# M1.net
KiCad netlist of a schematic drawn in Altium Designer
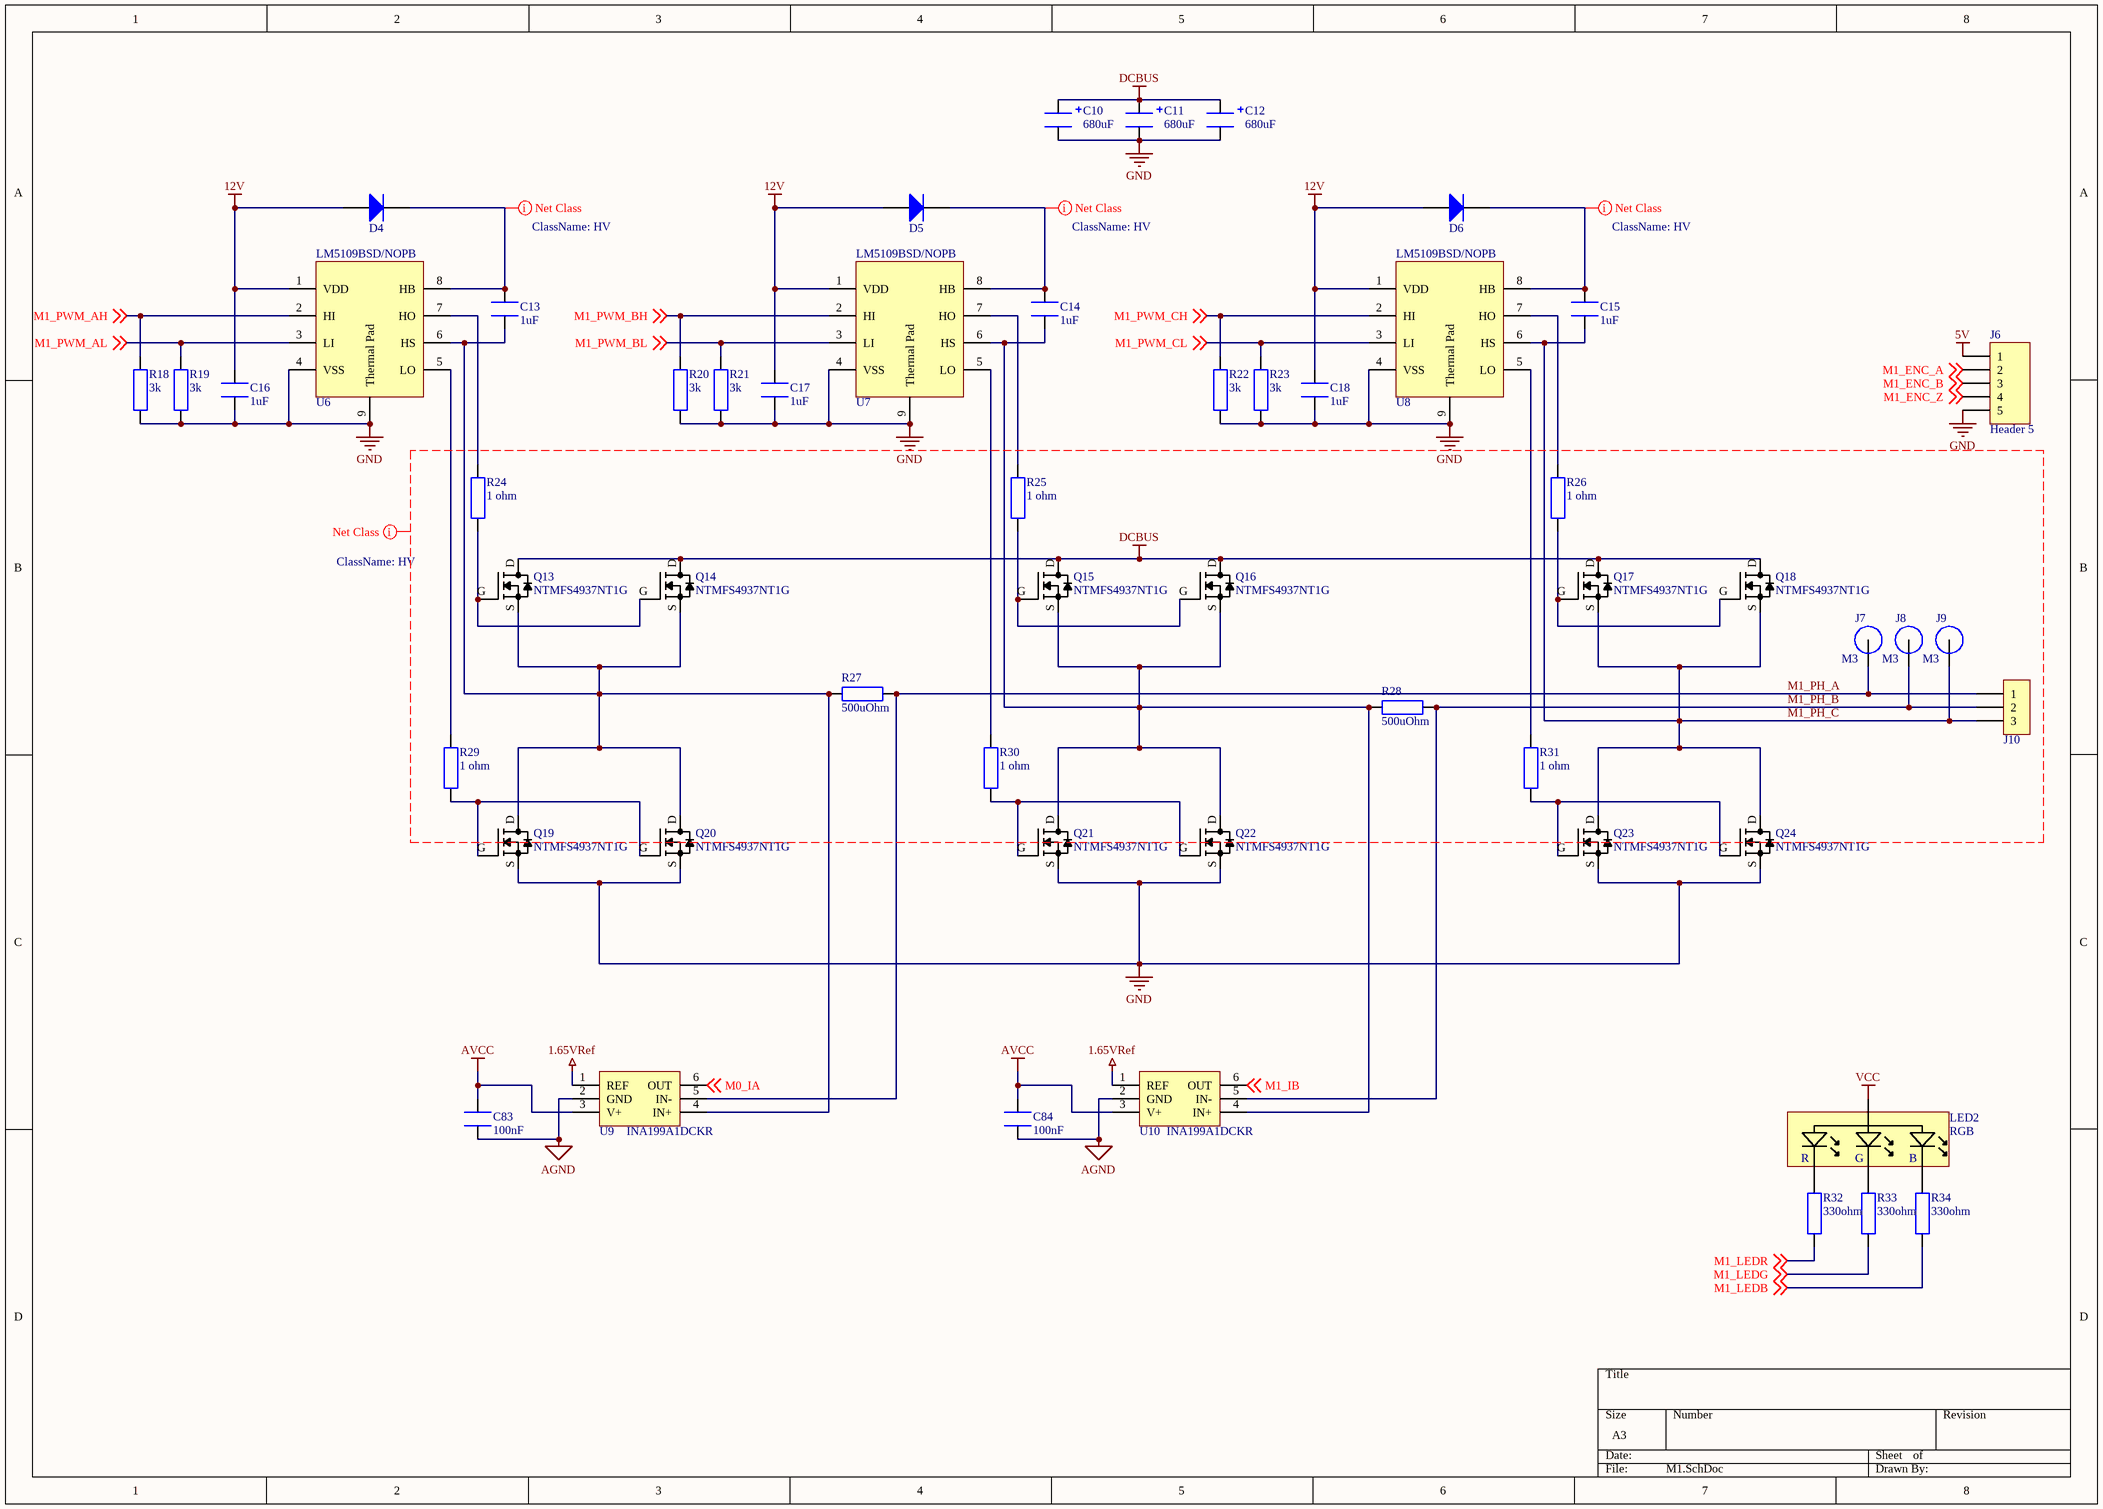
[diagram p0: M1.SchDoc]

(export (version "E")
  (design (tool "Eeschema 10.0.6"))
  (components
    (comp (ref "C10")
      (value "680uF")
      (footprint "CAPE10.0MM_Rad_10x14mm")
      (description "CAP, ALU ELEC, 680UF, 35V, RAD")
      (fields (field (name "Comment") "35ZLH680MEFC10X23"))
      (libsource (lib "CustomComponents") (part "35ZLH680MEFC10X23"))
    )
    (comp (ref "C11")
      (value "680uF")
      (footprint "CAPE10.0MM_Rad_10x14mm")
      (description "CAP, ALU ELEC, 680UF, 35V, RAD")
      (fields (field (name "Comment") "35ZLH680MEFC10X23"))
      (libsource (lib "CustomComponents") (part "35ZLH680MEFC10X23"))
    )
    (comp (ref "C12")
      (value "680uF")
      (footprint "CAPE10.0MM_Rad_10x14mm")
      (description "CAP, ALU ELEC, 680UF, 35V, RAD")
      (fields (field (name "Comment") "35ZLH680MEFC10X23"))
      (libsource (lib "CustomComponents") (part "35ZLH680MEFC10X23"))
    )
    (comp (ref "C13")
      (value "1uF")
      (footprint "1608[0603]")
      (description "CAP, MLCC, X5R, 1UF, 16V, 0603")
      (fields (field (name "Comment") "MC0603X105K160"))
      (libsource (lib "CustomComponents") (part "MC0603X105K160"))
    )
    (comp (ref "C14")
      (value "1uF")
      (footprint "1608[0603]")
      (description "CAP, MLCC, X5R, 1UF, 16V, 0603")
      (fields (field (name "Comment") "MC0603X105K160"))
      (libsource (lib "CustomComponents") (part "MC0603X105K160"))
    )
    (comp (ref "C15")
      (value "1uF")
      (footprint "1608[0603]")
      (description "CAP, MLCC, X5R, 1UF, 16V, 0603")
      (fields (field (name "Comment") "MC0603X105K160"))
      (libsource (lib "CustomComponents") (part "MC0603X105K160"))
    )
    (comp (ref "C16")
      (value "1uF")
      (footprint "1608[0603]")
      (description "CAP, MLCC, X5R, 1UF, 16V, 0603")
      (fields (field (name "Comment") "MC0603X105K160"))
      (libsource (lib "CustomComponents") (part "MC0603X105K160"))
    )
    (comp (ref "C17")
      (value "1uF")
      (footprint "1608[0603]")
      (description "CAP, MLCC, X5R, 1UF, 16V, 0603")
      (fields (field (name "Comment") "MC0603X105K160"))
      (libsource (lib "CustomComponents") (part "MC0603X105K160"))
    )
    (comp (ref "C18")
      (value "1uF")
      (footprint "1608[0603]")
      (description "CAP, MLCC, X5R, 1UF, 16V, 0603")
      (fields (field (name "Comment") "MC0603X105K160"))
      (libsource (lib "CustomComponents") (part "MC0603X105K160"))
    )
    (comp (ref "C83")
      (value "100nF")
      (footprint "1608[0603]")
      (description "CAP, MLCC, X7R, 100NF, 16V, 0603")
      (fields (field (name "Comment") "MC0603B104K160CT"))
      (libsource (lib "CustomComponents") (part "MC0603B104K160CT"))
    )
    (comp (ref "C84")
      (value "100nF")
      (footprint "1608[0603]")
      (description "CAP, MLCC, X7R, 100NF, 16V, 0603")
      (fields (field (name "Comment") "MC0603B104K160CT"))
      (libsource (lib "CustomComponents") (part "MC0603B104K160CT"))
    )
    (comp (ref "D4")
      (value "RB521S30T1G")
      (footprint "SOD523F")
      (description "DIODE, SCHOTTKY, 200MA, 30V")
      (libsource (lib "CustomComponents") (part "RB521S30T1G"))
    )
    (comp (ref "D5")
      (value "RB521S30T1G")
      (footprint "SOD523F")
      (description "DIODE, SCHOTTKY, 200MA, 30V")
      (libsource (lib "CustomComponents") (part "RB521S30T1G"))
    )
    (comp (ref "D6")
      (value "RB521S30T1G")
      (footprint "SOD523F")
      (description "DIODE, SCHOTTKY, 200MA, 30V")
      (libsource (lib "CustomComponents") (part "RB521S30T1G"))
    )
    (comp (ref "J6")
      (value "Header 5")
      (footprint "HDR1X5")
      (description "Header, 5-Pin")
      (fields (field (name "PUBLISHER") "Altium Limited"))
      (libsource (lib "Miscellaneous Connectors") (part "Header 5"))
    )
    (comp (ref "J7")
      (value "M3")
      (footprint "M3 Spade Hole")
      (description "M3 Spade Terminal")
      (libsource (lib "CustomComponents") (part "M3 Spade Terminal"))
    )
    (comp (ref "J8")
      (value "M3")
      (footprint "M3 Spade Hole")
      (description "M3 Spade Terminal")
      (libsource (lib "CustomComponents") (part "M3 Spade Terminal"))
    )
    (comp (ref "J9")
      (value "M3")
      (footprint "M3 Spade Hole")
      (description "M3 Spade Terminal")
      (libsource (lib "CustomComponents") (part "M3 Spade Terminal"))
    )
    (comp (ref "J10")
      (value "MC000051")
      (footprint "MC000051")
      (description "TERMINAL BLOCK, WIRE TO BRD, 3POS, 10AWG")
      (libsource (lib "CustomComponents") (part "MC000051"))
    )
    (comp (ref "LED2")
      (value "RGB")
      (footprint "ASMB-MTB1")
      (description "LED, HB, RGB, 0.09W, PLCC-4")
      (libsource (lib "CustomComponents") (part "ASMB-MTB1-0A3A2"))
    )
    (comp (ref "Q13")
      (value "NTMFS4937NT1G")
      (footprint "SO8FL")
      (description "MOSFET, N CH, 30V, 70A, SO-8 FL")
      (libsource (lib "CustomComponents") (part "NTMFS4937NT1G"))
    )
    (comp (ref "Q14")
      (value "NTMFS4937NT1G")
      (footprint "SO8FL")
      (description "MOSFET, N CH, 30V, 70A, SO-8 FL")
      (libsource (lib "CustomComponents") (part "NTMFS4937NT1G"))
    )
    (comp (ref "Q15")
      (value "NTMFS4937NT1G")
      (footprint "SO8FL")
      (description "MOSFET, N CH, 30V, 70A, SO-8 FL")
      (libsource (lib "CustomComponents") (part "NTMFS4937NT1G"))
    )
    (comp (ref "Q16")
      (value "NTMFS4937NT1G")
      (footprint "SO8FL")
      (description "MOSFET, N CH, 30V, 70A, SO-8 FL")
      (libsource (lib "CustomComponents") (part "NTMFS4937NT1G"))
    )
    (comp (ref "Q17")
      (value "NTMFS4937NT1G")
      (footprint "SO8FL")
      (description "MOSFET, N CH, 30V, 70A, SO-8 FL")
      (libsource (lib "CustomComponents") (part "NTMFS4937NT1G"))
    )
    (comp (ref "Q18")
      (value "NTMFS4937NT1G")
      (footprint "SO8FL")
      (description "MOSFET, N CH, 30V, 70A, SO-8 FL")
      (libsource (lib "CustomComponents") (part "NTMFS4937NT1G"))
    )
    (comp (ref "Q19")
      (value "NTMFS4937NT1G")
      (footprint "SO8FL")
      (description "MOSFET, N CH, 30V, 70A, SO-8 FL")
      (libsource (lib "CustomComponents") (part "NTMFS4937NT1G"))
    )
    (comp (ref "Q20")
      (value "NTMFS4937NT1G")
      (footprint "SO8FL")
      (description "MOSFET, N CH, 30V, 70A, SO-8 FL")
      (libsource (lib "CustomComponents") (part "NTMFS4937NT1G"))
    )
    (comp (ref "Q21")
      (value "NTMFS4937NT1G")
      (footprint "SO8FL")
      (description "MOSFET, N CH, 30V, 70A, SO-8 FL")
      (libsource (lib "CustomComponents") (part "NTMFS4937NT1G"))
    )
    (comp (ref "Q22")
      (value "NTMFS4937NT1G")
      (footprint "SO8FL")
      (description "MOSFET, N CH, 30V, 70A, SO-8 FL")
      (libsource (lib "CustomComponents") (part "NTMFS4937NT1G"))
    )
    (comp (ref "Q23")
      (value "NTMFS4937NT1G")
      (footprint "SO8FL")
      (description "MOSFET, N CH, 30V, 70A, SO-8 FL")
      (libsource (lib "CustomComponents") (part "NTMFS4937NT1G"))
    )
    (comp (ref "Q24")
      (value "NTMFS4937NT1G")
      (footprint "SO8FL")
      (description "MOSFET, N CH, 30V, 70A, SO-8 FL")
      (libsource (lib "CustomComponents") (part "NTMFS4937NT1G"))
    )
    (comp (ref "R18")
      (value "3k")
      (footprint "RESC1608X55N")
      (description "RESISTOR, 0603, 3K, 1%, ANTI SULFUR")
      (fields (field (name "Comment") "MCMR06X3001FTL"))
      (libsource (lib "CustomComponents") (part "MCMR06X3001FTL"))
    )
    (comp (ref "R19")
      (value "3k")
      (footprint "RESC1608X55N")
      (description "RESISTOR, 0603, 3K, 1%, ANTI SULFUR")
      (fields (field (name "Comment") "MCMR06X3001FTL"))
      (libsource (lib "CustomComponents") (part "MCMR06X3001FTL"))
    )
    (comp (ref "R20")
      (value "3k")
      (footprint "RESC1608X55N")
      (description "RESISTOR, 0603, 3K, 1%, ANTI SULFUR")
      (fields (field (name "Comment") "MCMR06X3001FTL"))
      (libsource (lib "CustomComponents") (part "MCMR06X3001FTL"))
    )
    (comp (ref "R21")
      (value "3k")
      (footprint "RESC1608X55N")
      (description "RESISTOR, 0603, 3K, 1%, ANTI SULFUR")
      (fields (field (name "Comment") "MCMR06X3001FTL"))
      (libsource (lib "CustomComponents") (part "MCMR06X3001FTL"))
    )
    (comp (ref "R22")
      (value "3k")
      (footprint "RESC1608X55N")
      (description "RESISTOR, 0603, 3K, 1%, ANTI SULFUR")
      (fields (field (name "Comment") "MCMR06X3001FTL"))
      (libsource (lib "CustomComponents") (part "MCMR06X3001FTL"))
    )
    (comp (ref "R23")
      (value "3k")
      (footprint "RESC1608X55N")
      (description "RESISTOR, 0603, 3K, 1%, ANTI SULFUR")
      (fields (field (name "Comment") "MCMR06X3001FTL"))
      (libsource (lib "CustomComponents") (part "MCMR06X3001FTL"))
    )
    (comp (ref "R24")
      (value "1 ohm")
      (footprint "RESC1608X55N")
      (description "RES, THICK FILM, 1OHM, 1%, 0.1W")
      (fields (field (name "Comment") "MCWR06W1R00FTL"))
      (libsource (lib "CustomComponents") (part "MCWR06W1R00FTL"))
    )
    (comp (ref "R25")
      (value "1 ohm")
      (footprint "RESC1608X55N")
      (description "RES, THICK FILM, 1OHM, 1%, 0.1W")
      (fields (field (name "Comment") "MCWR06W1R00FTL"))
      (libsource (lib "CustomComponents") (part "MCWR06W1R00FTL"))
    )
    (comp (ref "R26")
      (value "1 ohm")
      (footprint "RESC1608X55N")
      (description "RES, THICK FILM, 1OHM, 1%, 0.1W")
      (fields (field (name "Comment") "MCWR06W1R00FTL"))
      (libsource (lib "CustomComponents") (part "MCWR06W1R00FTL"))
    )
    (comp (ref "R27")
      (value "500uOhm")
      (footprint "RESC6332X70N")
      (description "RESISTOR, R0005, 2.0W, 1%")
      (fields (field (name "Comment") "TLR3A20DR0005FTDG"))
      (libsource (lib "CustomComponents") (part "TLR3A20DR0005FTDG"))
    )
    (comp (ref "R28")
      (value "500uOhm")
      (footprint "RESC6332X70N")
      (description "RESISTOR, R0005, 2.0W, 1%")
      (fields (field (name "Comment") "TLR3A20DR0005FTDG"))
      (libsource (lib "CustomComponents") (part "TLR3A20DR0005FTDG"))
    )
    (comp (ref "R29")
      (value "1 ohm")
      (footprint "RESC1608X55N")
      (description "RES, THICK FILM, 1OHM, 1%, 0.1W")
      (fields (field (name "Comment") "MCWR06W1R00FTL"))
      (libsource (lib "CustomComponents") (part "MCWR06W1R00FTL"))
    )
    (comp (ref "R30")
      (value "1 ohm")
      (footprint "RESC1608X55N")
      (description "RES, THICK FILM, 1OHM, 1%, 0.1W")
      (fields (field (name "Comment") "MCWR06W1R00FTL"))
      (libsource (lib "CustomComponents") (part "MCWR06W1R00FTL"))
    )
    (comp (ref "R31")
      (value "1 ohm")
      (footprint "RESC1608X55N")
      (description "RES, THICK FILM, 1OHM, 1%, 0.1W")
      (fields (field (name "Comment") "MCWR06W1R00FTL"))
      (libsource (lib "CustomComponents") (part "MCWR06W1R00FTL"))
    )
    (comp (ref "R32")
      (value "330ohm")
      (footprint "RESC1608X55N")
      (description "RES, THICK FILM, 330 OHM, 1%, 0.1W")
      (fields (field (name "Comment") "MCWR06X3300FTL"))
      (libsource (lib "CustomComponents") (part "MCWR06X3300FTL"))
    )
    (comp (ref "R33")
      (value "330ohm")
      (footprint "RESC1608X55N")
      (description "RES, THICK FILM, 330 OHM, 1%, 0.1W")
      (fields (field (name "Comment") "MCWR06X3300FTL"))
      (libsource (lib "CustomComponents") (part "MCWR06X3300FTL"))
    )
    (comp (ref "R34")
      (value "330ohm")
      (footprint "RESC1608X55N")
      (description "RES, THICK FILM, 330 OHM, 1%, 0.1W")
      (fields (field (name "Comment") "MCWR06X3300FTL"))
      (libsource (lib "CustomComponents") (part "MCWR06X3300FTL"))
    )
    (comp (ref "U6")
      (value "LM5109BSD/NOPB")
      (footprint "SON80P400X80_HS-9N")
      (description "DRIVER, MOSFET, HALF BRIDGE, WSON-8, 1A")
      (libsource (lib "CustomComponents") (part "LM5109BSD/NOPB"))
    )
    (comp (ref "U7")
      (value "LM5109BSD/NOPB")
      (footprint "SON80P400X80_HS-9N")
      (description "DRIVER, MOSFET, HALF BRIDGE, WSON-8, 1A")
      (libsource (lib "CustomComponents") (part "LM5109BSD/NOPB"))
    )
    (comp (ref "U8")
      (value "LM5109BSD/NOPB")
      (footprint "SON80P400X80_HS-9N")
      (description "DRIVER, MOSFET, HALF BRIDGE, WSON-8, 1A")
      (libsource (lib "CustomComponents") (part "LM5109BSD/NOPB"))
    )
    (comp (ref "U9")
      (value "INA199A1DCKR")
      (footprint "TSOP65P210X110-6N")
      (description "CURRENT SENSE AMP, 50V/V, 80KHZ")
      (libsource (lib "CustomComponents") (part "INA199A1DCKR"))
    )
    (comp (ref "U10")
      (value "INA199A1DCKR")
      (footprint "TSOP65P210X110-6N")
      (description "CURRENT SENSE AMP, 50V/V, 80KHZ")
      (libsource (lib "CustomComponents") (part "INA199A1DCKR"))
    )
  )
  (nets
    (net (code "1") (name "/M1_PH_A") (class "Default")
      (node (ref "J10") (pin "1") (pinfunction "1_1") (pintype "passive"))
      (node (ref "J7") (pin "1") (pinfunction "1_1") (pintype "passive"))
      (node (ref "R27") (pin "1") (pinfunction "0_1") (pintype "passive"))
      (node (ref "U9") (pin "5") (pinfunction "IN-_5") (pintype "passive"))
    )
    (net (code "2") (name "/M1_PH_B") (class "Default")
      (node (ref "J10") (pin "2") (pinfunction "2_2") (pintype "passive"))
      (node (ref "J8") (pin "1") (pinfunction "1_1") (pintype "passive"))
      (node (ref "R28") (pin "1") (pinfunction "0_1") (pintype "passive"))
      (node (ref "U10") (pin "5") (pinfunction "IN-_5") (pintype "passive"))
    )
    (net (code "3") (name "/M1_PH_C") (class "Default")
      (node (ref "C15") (pin "1") (pinfunction "1_1") (pintype "passive"))
      (node (ref "J10") (pin "3") (pinfunction "3_3") (pintype "passive"))
      (node (ref "J9") (pin "1") (pinfunction "1_1") (pintype "passive"))
      (node (ref "Q17") (pin "S") (pinfunction "S_S") (pintype "passive"))
      (node (ref "Q18") (pin "S") (pinfunction "S_S") (pintype "passive"))
      (node (ref "Q23") (pin "D") (pinfunction "D_D") (pintype "passive"))
      (node (ref "Q24") (pin "D") (pinfunction "D_D") (pintype "passive"))
      (node (ref "U8") (pin "6") (pinfunction "HS_6") (pintype "passive"))
    )
    (net (code "4") (name "1.65VRef") (class "Default")
      (node (ref "U10") (pin "1") (pinfunction "REF_1") (pintype "passive"))
      (node (ref "U9") (pin "1") (pinfunction "REF_1") (pintype "passive"))
    )
    (net (code "5") (name "5V") (class "Default")
      (node (ref "J6") (pin "1") (pinfunction "1_1") (pintype "passive"))
    )
    (net (code "6") (name "12V") (class "Default")
      (node (ref "C16") (pin "2") (pinfunction "2_2") (pintype "passive"))
      (node (ref "C17") (pin "2") (pinfunction "2_2") (pintype "passive"))
      (node (ref "C18") (pin "2") (pinfunction "2_2") (pintype "passive"))
      (node (ref "D4") (pin "A") (pinfunction "A_A") (pintype "passive"))
      (node (ref "D5") (pin "A") (pinfunction "A_A") (pintype "passive"))
      (node (ref "D6") (pin "A") (pinfunction "A_A") (pintype "passive"))
      (node (ref "U6") (pin "1") (pinfunction "VDD_1") (pintype "passive"))
      (node (ref "U7") (pin "1") (pinfunction "VDD_1") (pintype "passive"))
      (node (ref "U8") (pin "1") (pinfunction "VDD_1") (pintype "passive"))
    )
    (net (code "7") (name "AGND") (class "Default")
      (node (ref "C83") (pin "1") (pinfunction "1_1") (pintype "passive"))
      (node (ref "C84") (pin "1") (pinfunction "1_1") (pintype "passive"))
      (node (ref "U10") (pin "2") (pinfunction "GND_2") (pintype "passive"))
      (node (ref "U9") (pin "2") (pinfunction "GND_2") (pintype "passive"))
    )
    (net (code "8") (name "AVCC") (class "Default")
      (node (ref "C83") (pin "2") (pinfunction "2_2") (pintype "passive"))
      (node (ref "C84") (pin "2") (pinfunction "2_2") (pintype "passive"))
      (node (ref "U10") (pin "3") (pinfunction "V+_3") (pintype "passive"))
      (node (ref "U9") (pin "3") (pinfunction "V+_3") (pintype "passive"))
    )
    (net (code "9") (name "DCBUS") (class "Default")
      (node (ref "C10") (pin "1") (pinfunction "1_1") (pintype "passive"))
      (node (ref "C11") (pin "1") (pinfunction "1_1") (pintype "passive"))
      (node (ref "C12") (pin "1") (pinfunction "1_1") (pintype "passive"))
      (node (ref "Q13") (pin "D") (pinfunction "D_D") (pintype "passive"))
      (node (ref "Q14") (pin "D") (pinfunction "D_D") (pintype "passive"))
      (node (ref "Q15") (pin "D") (pinfunction "D_D") (pintype "passive"))
      (node (ref "Q16") (pin "D") (pinfunction "D_D") (pintype "passive"))
      (node (ref "Q17") (pin "D") (pinfunction "D_D") (pintype "passive"))
      (node (ref "Q18") (pin "D") (pinfunction "D_D") (pintype "passive"))
    )
    (net (code "10") (name "GND") (class "Default")
      (node (ref "C10") (pin "2") (pinfunction "2_2") (pintype "passive"))
      (node (ref "C11") (pin "2") (pinfunction "2_2") (pintype "passive"))
      (node (ref "C12") (pin "2") (pinfunction "2_2") (pintype "passive"))
      (node (ref "C16") (pin "1") (pinfunction "1_1") (pintype "passive"))
      (node (ref "C17") (pin "1") (pinfunction "1_1") (pintype "passive"))
      (node (ref "C18") (pin "1") (pinfunction "1_1") (pintype "passive"))
      (node (ref "J6") (pin "5") (pinfunction "5_5") (pintype "passive"))
      (node (ref "Q19") (pin "S") (pinfunction "S_S") (pintype "passive"))
      (node (ref "Q20") (pin "S") (pinfunction "S_S") (pintype "passive"))
      (node (ref "Q21") (pin "S") (pinfunction "S_S") (pintype "passive"))
      (node (ref "Q22") (pin "S") (pinfunction "S_S") (pintype "passive"))
      (node (ref "Q23") (pin "S") (pinfunction "S_S") (pintype "passive"))
      (node (ref "Q24") (pin "S") (pinfunction "S_S") (pintype "passive"))
      (node (ref "R18") (pin "1") (pinfunction "0_1") (pintype "passive"))
      (node (ref "R19") (pin "1") (pinfunction "0_1") (pintype "passive"))
      (node (ref "R20") (pin "1") (pinfunction "0_1") (pintype "passive"))
      (node (ref "R21") (pin "1") (pinfunction "0_1") (pintype "passive"))
      (node (ref "R22") (pin "1") (pinfunction "0_1") (pintype "passive"))
      (node (ref "R23") (pin "1") (pinfunction "0_1") (pintype "passive"))
      (node (ref "U6") (pin "4") (pinfunction "VSS_4") (pintype "passive"))
      (node (ref "U6") (pin "9") (pinfunction "Thermal_Pad_9") (pintype "passive"))
      (node (ref "U7") (pin "4") (pinfunction "VSS_4") (pintype "passive"))
      (node (ref "U7") (pin "9") (pinfunction "Thermal_Pad_9") (pintype "passive"))
      (node (ref "U8") (pin "4") (pinfunction "VSS_4") (pintype "passive"))
      (node (ref "U8") (pin "9") (pinfunction "Thermal_Pad_9") (pintype "passive"))
    )
    (net (code "11") (name "M0_IA") (class "Default")
      (node (ref "U9") (pin "6") (pinfunction "OUT_6") (pintype "passive"))
    )
    (net (code "12") (name "M1_ENC_A") (class "Default")
      (node (ref "J6") (pin "2") (pinfunction "2_2") (pintype "passive"))
    )
    (net (code "13") (name "M1_ENC_B") (class "Default")
      (node (ref "J6") (pin "3") (pinfunction "3_3") (pintype "passive"))
    )
    (net (code "14") (name "M1_ENC_Z") (class "Default")
      (node (ref "J6") (pin "4") (pinfunction "4_4") (pintype "passive"))
    )
    (net (code "15") (name "M1_IB") (class "Default")
      (node (ref "U10") (pin "6") (pinfunction "OUT_6") (pintype "passive"))
    )
    (net (code "16") (name "M1_LEDB") (class "Default")
      (node (ref "R34") (pin "2") (pinfunction "0_2") (pintype "passive"))
    )
    (net (code "17") (name "M1_LEDG") (class "Default")
      (node (ref "R33") (pin "2") (pinfunction "0_2") (pintype "passive"))
    )
    (net (code "18") (name "M1_LEDR") (class "Default")
      (node (ref "R32") (pin "2") (pinfunction "0_2") (pintype "passive"))
    )
    (net (code "19") (name "M1_PWM_AH") (class "Default")
      (node (ref "R18") (pin "2") (pinfunction "0_2") (pintype "passive"))
      (node (ref "U6") (pin "2") (pinfunction "HI_2") (pintype "passive"))
    )
    (net (code "20") (name "M1_PWM_AL") (class "Default")
      (node (ref "R19") (pin "2") (pinfunction "0_2") (pintype "passive"))
      (node (ref "U6") (pin "3") (pinfunction "LI_3") (pintype "passive"))
    )
    (net (code "21") (name "M1_PWM_BH") (class "Default")
      (node (ref "R20") (pin "2") (pinfunction "0_2") (pintype "passive"))
      (node (ref "U7") (pin "2") (pinfunction "HI_2") (pintype "passive"))
    )
    (net (code "22") (name "M1_PWM_BL") (class "Default")
      (node (ref "R21") (pin "2") (pinfunction "0_2") (pintype "passive"))
      (node (ref "U7") (pin "3") (pinfunction "LI_3") (pintype "passive"))
    )
    (net (code "23") (name "M1_PWM_CH") (class "Default")
      (node (ref "R22") (pin "2") (pinfunction "0_2") (pintype "passive"))
      (node (ref "U8") (pin "2") (pinfunction "HI_2") (pintype "passive"))
    )
    (net (code "24") (name "M1_PWM_CL") (class "Default")
      (node (ref "R23") (pin "2") (pinfunction "0_2") (pintype "passive"))
      (node (ref "U8") (pin "3") (pinfunction "LI_3") (pintype "passive"))
    )
    (net (code "25") (name "Net-(LED2-B)") (class "Default")
      (node (ref "LED2") (pin "3") (pinfunction "B_3") (pintype "passive"))
      (node (ref "R34") (pin "1") (pinfunction "0_1") (pintype "passive"))
    )
    (net (code "26") (name "Net-(LED2-G)") (class "Default")
      (node (ref "LED2") (pin "2") (pinfunction "G_2") (pintype "passive"))
      (node (ref "R33") (pin "1") (pinfunction "0_1") (pintype "passive"))
    )
    (net (code "27") (name "Net-(LED2-R)") (class "Default")
      (node (ref "LED2") (pin "1") (pinfunction "R_1") (pintype "passive"))
      (node (ref "R32") (pin "1") (pinfunction "0_1") (pintype "passive"))
    )
    (net (code "28") (name "Net-(Q13-PadG)") (class "Default")
      (node (ref "Q13") (pin "G") (pinfunction "G_G") (pintype "passive"))
      (node (ref "Q14") (pin "G") (pinfunction "G_G") (pintype "passive"))
      (node (ref "R24") (pin "1") (pinfunction "0_1") (pintype "passive"))
    )
    (net (code "29") (name "Net-(Q15-PadG)") (class "Default")
      (node (ref "Q15") (pin "G") (pinfunction "G_G") (pintype "passive"))
      (node (ref "Q16") (pin "G") (pinfunction "G_G") (pintype "passive"))
      (node (ref "R25") (pin "1") (pinfunction "0_1") (pintype "passive"))
    )
    (net (code "30") (name "Net-(Q17-PadG)") (class "Default")
      (node (ref "Q17") (pin "G") (pinfunction "G_G") (pintype "passive"))
      (node (ref "Q18") (pin "G") (pinfunction "G_G") (pintype "passive"))
      (node (ref "R26") (pin "1") (pinfunction "0_1") (pintype "passive"))
    )
    (net (code "31") (name "Net-(Q19-PadG)") (class "Default")
      (node (ref "Q19") (pin "G") (pinfunction "G_G") (pintype "passive"))
      (node (ref "Q20") (pin "G") (pinfunction "G_G") (pintype "passive"))
      (node (ref "R29") (pin "1") (pinfunction "0_1") (pintype "passive"))
    )
    (net (code "32") (name "Net-(Q21-PadG)") (class "Default")
      (node (ref "Q21") (pin "G") (pinfunction "G_G") (pintype "passive"))
      (node (ref "Q22") (pin "G") (pinfunction "G_G") (pintype "passive"))
      (node (ref "R30") (pin "1") (pinfunction "0_1") (pintype "passive"))
    )
    (net (code "33") (name "Net-(Q23-PadG)") (class "Default")
      (node (ref "Q23") (pin "G") (pinfunction "G_G") (pintype "passive"))
      (node (ref "Q24") (pin "G") (pinfunction "G_G") (pintype "passive"))
      (node (ref "R31") (pin "1") (pinfunction "0_1") (pintype "passive"))
    )
    (net (code "34") (name "Net-(U6-HB)") (class "Default")
      (node (ref "C13") (pin "2") (pinfunction "2_2") (pintype "passive"))
      (node (ref "D4") (pin "K") (pinfunction "K_K") (pintype "passive"))
      (node (ref "U6") (pin "8") (pinfunction "HB_8") (pintype "passive"))
    )
    (net (code "35") (name "Net-(U6-HO)") (class "Default")
      (node (ref "R24") (pin "2") (pinfunction "0_2") (pintype "passive"))
      (node (ref "U6") (pin "7") (pinfunction "HO_7") (pintype "passive"))
    )
    (net (code "36") (name "Net-(U6-HS)") (class "Default")
      (node (ref "C13") (pin "1") (pinfunction "1_1") (pintype "passive"))
      (node (ref "Q13") (pin "S") (pinfunction "S_S") (pintype "passive"))
      (node (ref "Q14") (pin "S") (pinfunction "S_S") (pintype "passive"))
      (node (ref "Q19") (pin "D") (pinfunction "D_D") (pintype "passive"))
      (node (ref "Q20") (pin "D") (pinfunction "D_D") (pintype "passive"))
      (node (ref "R27") (pin "2") (pinfunction "0_2") (pintype "passive"))
      (node (ref "U6") (pin "6") (pinfunction "HS_6") (pintype "passive"))
      (node (ref "U9") (pin "4") (pinfunction "IN+_4") (pintype "passive"))
    )
    (net (code "37") (name "Net-(U6-LO)") (class "Default")
      (node (ref "R29") (pin "2") (pinfunction "0_2") (pintype "passive"))
      (node (ref "U6") (pin "5") (pinfunction "LO_5") (pintype "passive"))
    )
    (net (code "38") (name "Net-(U7-HB)") (class "Default")
      (node (ref "C14") (pin "2") (pinfunction "2_2") (pintype "passive"))
      (node (ref "D5") (pin "K") (pinfunction "K_K") (pintype "passive"))
      (node (ref "U7") (pin "8") (pinfunction "HB_8") (pintype "passive"))
    )
    (net (code "39") (name "Net-(U7-HO)") (class "Default")
      (node (ref "R25") (pin "2") (pinfunction "0_2") (pintype "passive"))
      (node (ref "U7") (pin "7") (pinfunction "HO_7") (pintype "passive"))
    )
    (net (code "40") (name "Net-(U7-LO)") (class "Default")
      (node (ref "R30") (pin "2") (pinfunction "0_2") (pintype "passive"))
      (node (ref "U7") (pin "5") (pinfunction "LO_5") (pintype "passive"))
    )
    (net (code "41") (name "Net-(U8-HB)") (class "Default")
      (node (ref "C15") (pin "2") (pinfunction "2_2") (pintype "passive"))
      (node (ref "D6") (pin "K") (pinfunction "K_K") (pintype "passive"))
      (node (ref "U8") (pin "8") (pinfunction "HB_8") (pintype "passive"))
    )
    (net (code "42") (name "Net-(U8-HO)") (class "Default")
      (node (ref "R26") (pin "2") (pinfunction "0_2") (pintype "passive"))
      (node (ref "U8") (pin "7") (pinfunction "HO_7") (pintype "passive"))
    )
    (net (code "43") (name "Net-(U8-LO)") (class "Default")
      (node (ref "R31") (pin "2") (pinfunction "0_2") (pintype "passive"))
      (node (ref "U8") (pin "5") (pinfunction "LO_5") (pintype "passive"))
    )
    (net (code "44") (name "Net-(U10-IN+)") (class "Default")
      (node (ref "C14") (pin "1") (pinfunction "1_1") (pintype "passive"))
      (node (ref "Q15") (pin "S") (pinfunction "S_S") (pintype "passive"))
      (node (ref "Q16") (pin "S") (pinfunction "S_S") (pintype "passive"))
      (node (ref "Q21") (pin "D") (pinfunction "D_D") (pintype "passive"))
      (node (ref "Q22") (pin "D") (pinfunction "D_D") (pintype "passive"))
      (node (ref "R28") (pin "2") (pinfunction "0_2") (pintype "passive"))
      (node (ref "U10") (pin "4") (pinfunction "IN+_4") (pintype "passive"))
      (node (ref "U7") (pin "6") (pinfunction "HS_6") (pintype "passive"))
    )
    (net (code "45") (name "VCC") (class "Default")
      (node (ref "LED2") (pin "4") (pinfunction "A_4") (pintype "passive"))
    )
  )
)
